# LEDDriver.net
KiCad netlist of a schematic drawn in EAGLE
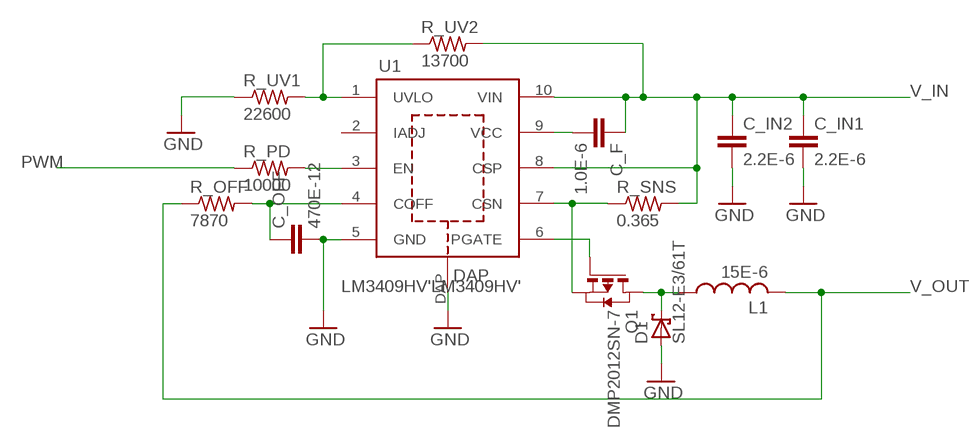
[diagram p0: schematic, sheet 1]

(export (version "E")
  (design (tool "Eeschema 10.0.6"))
  (components
    (comp (ref "C_F")
      (value "1.0E-6")
      (footprint "eagle-import:C0603")
      (libsource (lib "eagle-import") (part "CC0603"))
    )
    (comp (ref "C_IN1")
      (value "2.2E-6")
      (footprint "eagle-import:C0603")
      (libsource (lib "eagle-import") (part "CC0603"))
    )
    (comp (ref "C_IN2")
      (value "2.2E-6")
      (footprint "eagle-import:C0603")
      (libsource (lib "eagle-import") (part "CC0603"))
    )
    (comp (ref "C_OFF")
      (value "470E-12")
      (footprint "eagle-import:C0402")
      (libsource (lib "eagle-import") (part "CC0402"))
    )
    (comp (ref "D1")
      (value "SL12-E3/61T")
      (footprint "eagle-import:SL12-E3_61T")
      (libsource (lib "eagle-import") (part "SL12-E3/61T"))
    )
    (comp (ref "L1")
      (value "15E-6")
      (footprint "eagle-import:SRN8040")
      (libsource (lib "eagle-import") (part "SRN8040"))
    )
    (comp (ref "Q1")
      (value "DMP2012SN-7")
      (footprint "eagle-import:DMP2012SN-7")
      (libsource (lib "eagle-import") (part "DMP2012SN-7"))
    )
    (comp (ref "R_OFF")
      (value "7870")
      (footprint "eagle-import:R0603")
      (libsource (lib "eagle-import") (part "R-US_R0603"))
    )
    (comp (ref "R_PD")
      (value "10000")
      (footprint "eagle-import:R0603")
      (libsource (lib "eagle-import") (part "R-US_R0603"))
    )
    (comp (ref "R_SNS")
      (value "0.365")
      (footprint "eagle-import:R2512")
      (libsource (lib "eagle-import") (part "R-US_R2512"))
    )
    (comp (ref "R_UV1")
      (value "22600")
      (footprint "eagle-import:R0603")
      (libsource (lib "eagle-import") (part "R-US_R0603"))
    )
    (comp (ref "R_UV2")
      (value "13700")
      (footprint "eagle-import:R0603")
      (libsource (lib "eagle-import") (part "R-US_R0603"))
    )
    (comp (ref "U1")
      (value "LM3409HV'LM3409HV'")
      (footprint "eagle-import:VSSOP-10")
      (libsource (lib "eagle-import") (part "LM3409HV'LM3409HV'"))
    )
  )
  (nets
    (net (code "1") (name "/PWM") (class "Default")
      (node (ref "R_PD") (pin "1") (pinfunction "1_1") (pintype "passive"))
    )
    (net (code "2") (name "/V_IN") (class "Default")
      (node (ref "C_F") (pin "1") (pinfunction "1_1") (pintype "passive"))
      (node (ref "C_IN1") (pin "1") (pinfunction "1_1") (pintype "passive"))
      (node (ref "C_IN2") (pin "1") (pinfunction "1_1") (pintype "passive"))
      (node (ref "R_SNS") (pin "2") (pinfunction "2_2") (pintype "passive"))
      (node (ref "R_UV2") (pin "2") (pinfunction "2_2") (pintype "passive"))
      (node (ref "U1") (pin "10") (pinfunction "VIN_10") (pintype "bidirectional"))
      (node (ref "U1") (pin "8") (pinfunction "CSP_8") (pintype "bidirectional"))
    )
    (net (code "3") (name "/V_OUT") (class "Default")
      (node (ref "L1") (pin "2") (pinfunction "2_2") (pintype "passive"))
      (node (ref "R_OFF") (pin "1") (pinfunction "1_1") (pintype "passive"))
    )
    (net (code "4") (name "GND") (class "Default")
      (node (ref "C_IN1") (pin "2") (pinfunction "2_2") (pintype "passive"))
      (node (ref "C_IN2") (pin "2") (pinfunction "2_2") (pintype "passive"))
      (node (ref "C_OFF") (pin "2") (pinfunction "2_2") (pintype "passive"))
      (node (ref "D1") (pin "2") (pinfunction "A_2") (pintype "passive"))
      (node (ref "R_UV1") (pin "1") (pinfunction "1_1") (pintype "passive"))
      (node (ref "U1") (pin "5") (pinfunction "GND_5") (pintype "bidirectional"))
      (node (ref "U1") (pin "DAP") (pinfunction "DAP_DAP") (pintype "bidirectional"))
    )
    (net (code "5") (name "Net-(D1-C)") (class "Default")
      (node (ref "D1") (pin "1") (pinfunction "C_1") (pintype "passive"))
      (node (ref "L1") (pin "1") (pinfunction "1_1") (pintype "passive"))
      (node (ref "Q1") (pin "1") (pinfunction "D_1") (pintype "passive"))
    )
    (net (code "6") (name "Net-(Q1-G)") (class "Default")
      (node (ref "Q1") (pin "2") (pinfunction "G_2") (pintype "passive"))
      (node (ref "U1") (pin "6") (pinfunction "PGATE_6") (pintype "bidirectional"))
    )
    (net (code "7") (name "Net-(Q1-S)") (class "Default")
      (node (ref "Q1") (pin "3") (pinfunction "S_3") (pintype "passive"))
      (node (ref "R_SNS") (pin "1") (pinfunction "1_1") (pintype "passive"))
      (node (ref "U1") (pin "7") (pinfunction "CSN_7") (pintype "bidirectional"))
    )
    (net (code "8") (name "Net-(U1-COFF)") (class "Default")
      (node (ref "C_OFF") (pin "1") (pinfunction "1_1") (pintype "passive"))
      (node (ref "R_OFF") (pin "2") (pinfunction "2_2") (pintype "passive"))
      (node (ref "U1") (pin "4") (pinfunction "COFF_4") (pintype "bidirectional"))
    )
    (net (code "9") (name "Net-(U1-EN)") (class "Default")
      (node (ref "R_PD") (pin "2") (pinfunction "2_2") (pintype "passive"))
      (node (ref "U1") (pin "3") (pinfunction "EN_3") (pintype "bidirectional"))
    )
    (net (code "10") (name "Net-(U1-UVLO)") (class "Default")
      (node (ref "R_UV1") (pin "2") (pinfunction "2_2") (pintype "passive"))
      (node (ref "R_UV2") (pin "1") (pinfunction "1_1") (pintype "passive"))
      (node (ref "U1") (pin "1") (pinfunction "UVLO_1") (pintype "bidirectional"))
    )
    (net (code "11") (name "Net-(U1-VCC)") (class "Default")
      (node (ref "C_F") (pin "2") (pinfunction "2_2") (pintype "passive"))
      (node (ref "U1") (pin "9") (pinfunction "VCC_9") (pintype "bidirectional"))
    )
    (net (code "12") (name "unconnected-(U1-IADJ-Pad2)") (class "Default")
      (node (ref "U1") (pin "2") (pinfunction "IADJ_2") (pintype "bidirectional"))
    )
  )
)
